# Schematic_DeLonghi_CP_structured.net
KiCad netlist of a schematic drawn in EasyEDA
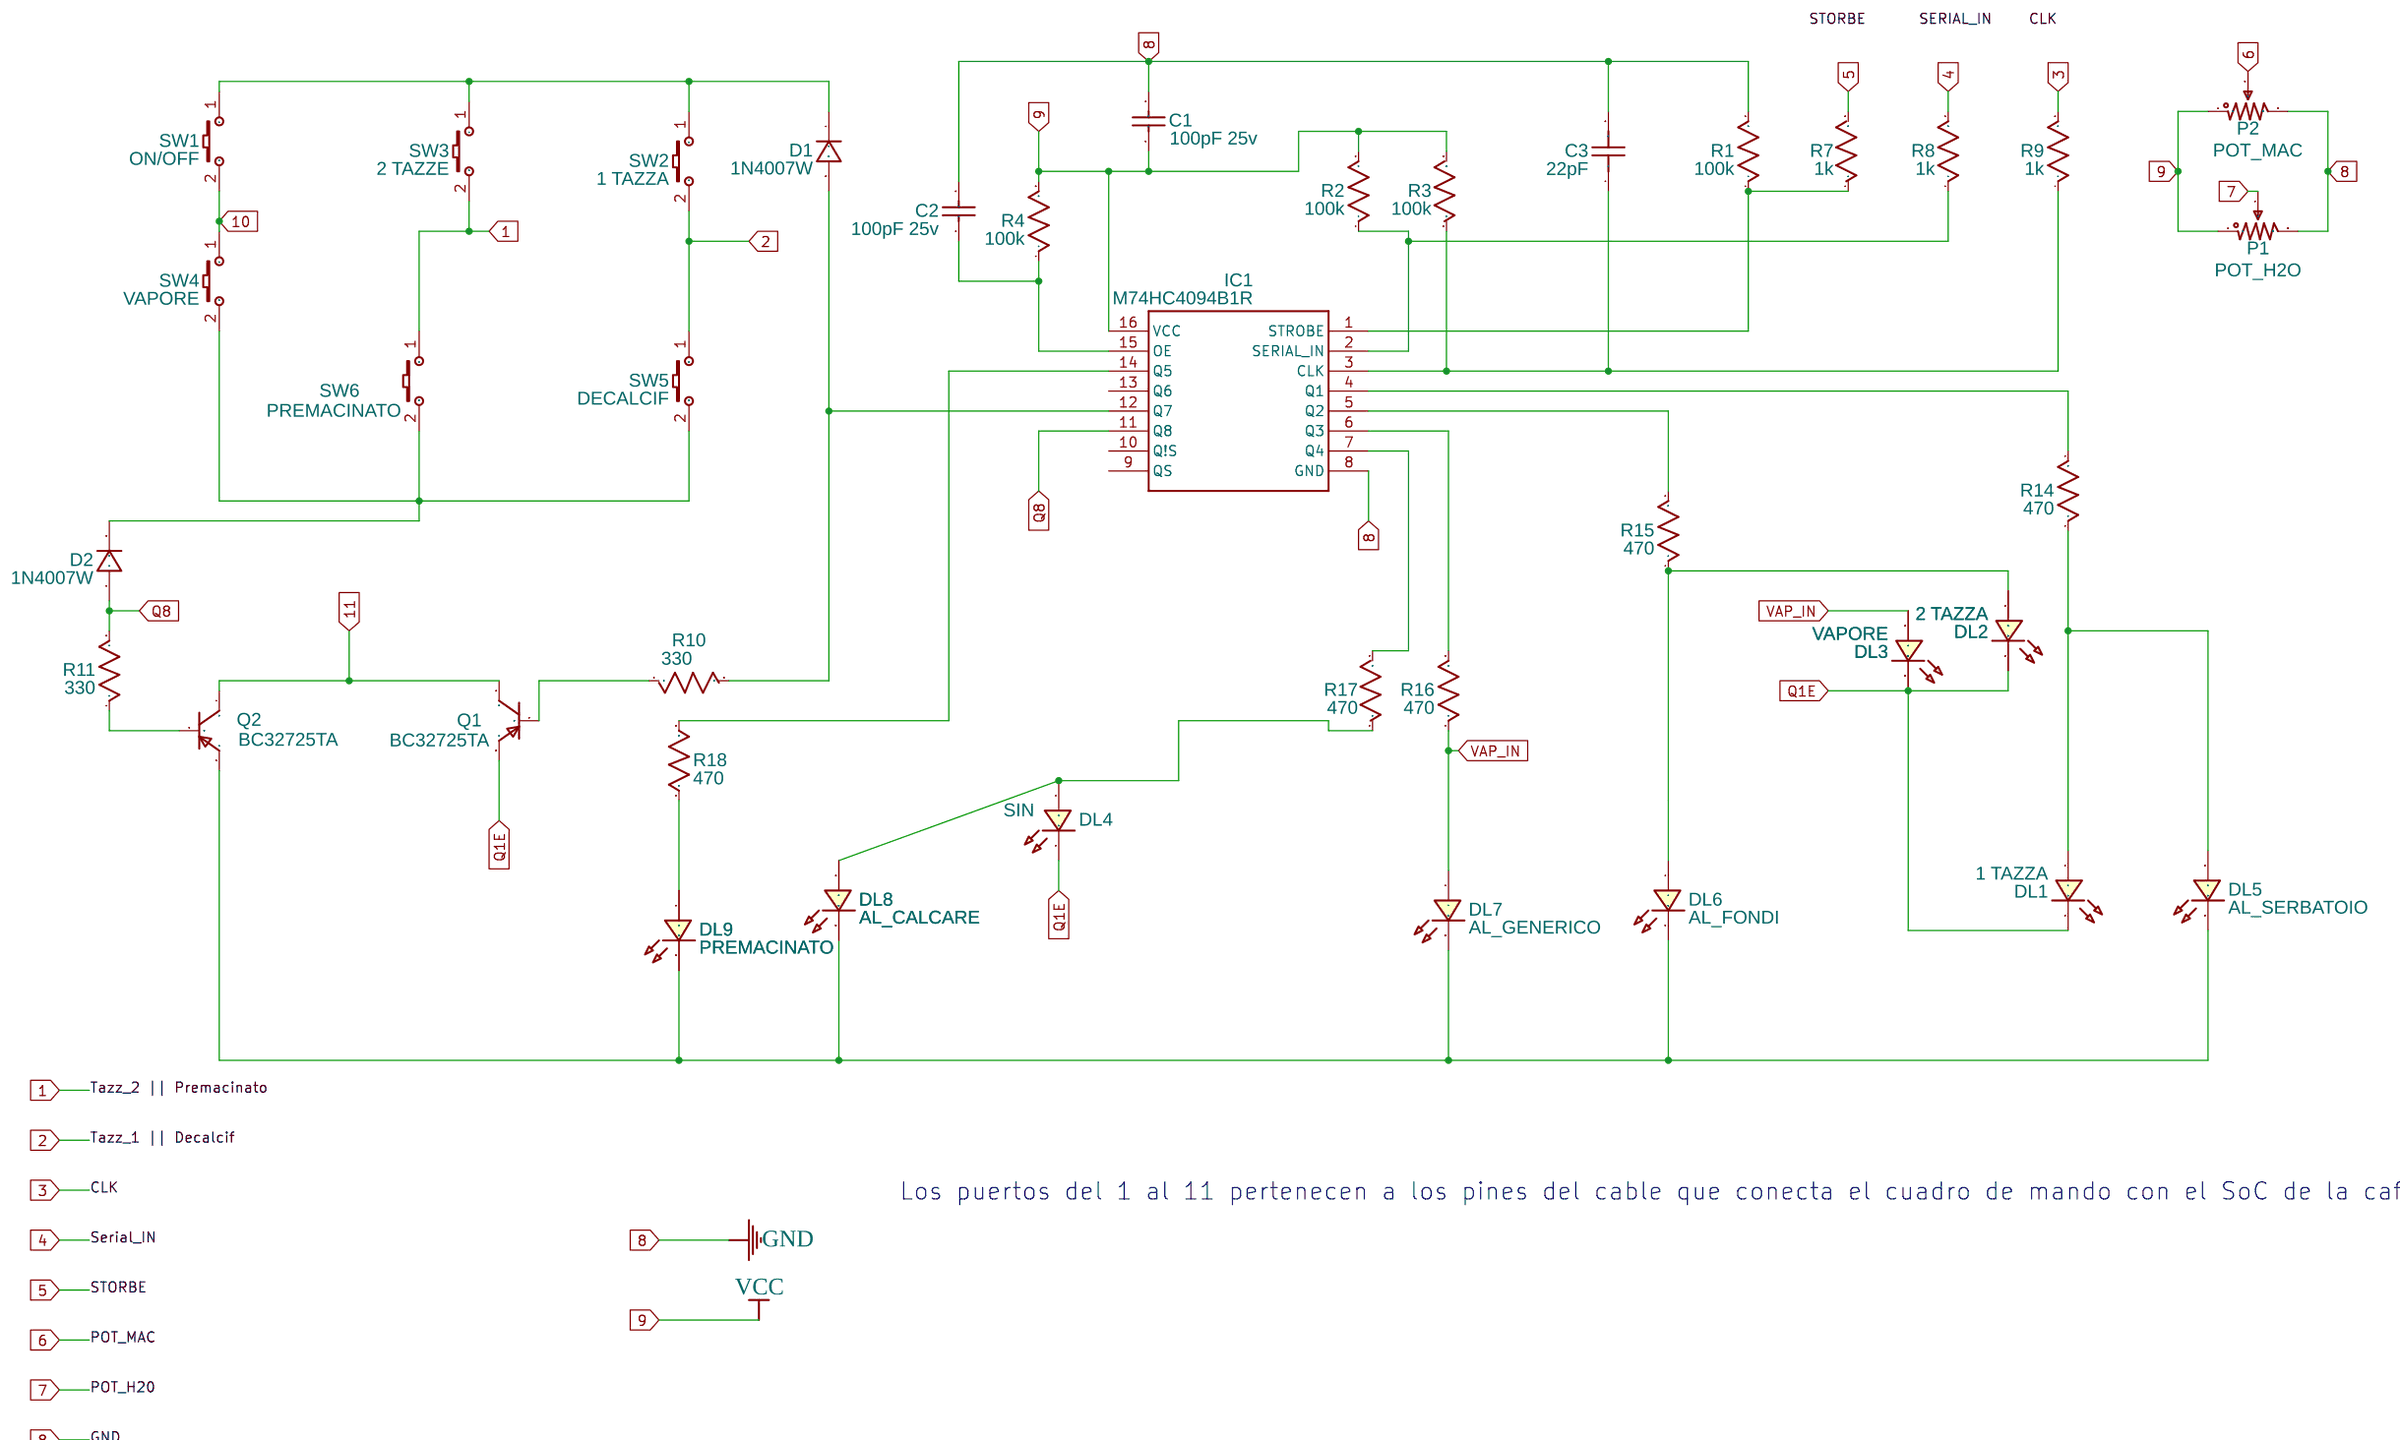
[diagram p0: schematic sheet]

(export (version "E")
  (design (tool "Eeschema 10.0.6"))
  (components
    (comp (ref "C1") (value "100pF 25v") (libsource (lib "") (part "100pF (101) 25V_1")))
    (comp (ref "C2") (value "100pF 25v") (libsource (lib "") (part "100pF (101) 25V")))
    (comp (ref "C3")
      (value "22pF")
      (fields
        (field (name "BOM_Manufacturer Part") "08051A220JAT2A")
        (field (name "BOM_Supplier Part") "C382073")
      )
      (libsource (lib "") (part "08051A220JAT2A"))
    )
    (comp (ref "D1")
      (value "1N4007W")
      (fields (field (name "BOM_Supplier Part") "C328592"))
      (libsource (lib "") (part "1N4007W"))
    )
    (comp (ref "D2")
      (value "1N4007W")
      (fields (field (name "BOM_Supplier Part") "C328592"))
      (libsource (lib "") (part "1N4007W"))
    )
    (comp (ref "DL1")
      (value "1 TAZZA")
      (fields
        (field (name "BOM_Manufacturer Part") "19-217/R6C-AL1M2VY/3T")
        (field (name "BOM_Supplier Part") "C72044")
      )
      (libsource (lib "") (part "LED-0603_R_1"))
    )
    (comp (ref "DL2")
      (value "2 TAZZA")
      (fields
        (field (name "BOM_Manufacturer Part") "19-217/R6C-AL1M2VY/3T")
        (field (name "BOM_Supplier Part") "C72044")
      )
      (libsource (lib "") (part "LED-0603_R_1"))
    )
    (comp (ref "DL3")
      (value "VAPORE")
      (fields
        (field (name "BOM_Manufacturer Part") "19-217/R6C-AL1M2VY/3T")
        (field (name "BOM_Supplier Part") "C72044")
      )
      (libsource (lib "") (part "LED-0603_R_1"))
    )
    (comp (ref "DL4")
      (value "SIN")
      (fields
        (field (name "BOM_Manufacturer Part") "19-217/R6C-AL1M2VY/3T")
        (field (name "BOM_Supplier Part") "C72044")
      )
      (libsource (lib "") (part "LED-0603_R"))
    )
    (comp (ref "DL5")
      (value "AL_SERBATOIO")
      (fields
        (field (name "BOM_Manufacturer Part") "19-217/R6C-AL1M2VY/3T")
        (field (name "BOM_Supplier Part") "C72044")
      )
      (libsource (lib "") (part "LED-0603_R"))
    )
    (comp (ref "DL6")
      (value "AL_FONDI")
      (fields
        (field (name "BOM_Manufacturer Part") "19-217/R6C-AL1M2VY/3T")
        (field (name "BOM_Supplier Part") "C72044")
      )
      (libsource (lib "") (part "LED-0603_R"))
    )
    (comp (ref "DL7")
      (value "AL_GENERICO")
      (fields
        (field (name "BOM_Manufacturer Part") "19-217/R6C-AL1M2VY/3T")
        (field (name "BOM_Supplier Part") "C72044")
      )
      (libsource (lib "") (part "LED-0603_R"))
    )
    (comp (ref "DL8")
      (value "AL_CALCARE")
      (fields
        (field (name "BOM_Manufacturer Part") "19-217/R6C-AL1M2VY/3T")
        (field (name "BOM_Supplier Part") "C72044")
      )
      (libsource (lib "") (part "LED-0603_R"))
    )
    (comp (ref "DL9")
      (value "PREMACINATO")
      (fields
        (field (name "BOM_Manufacturer Part") "19-217/R6C-AL1M2VY/3T")
        (field (name "BOM_Supplier Part") "C72044")
      )
      (libsource (lib "") (part "LED-0603_R"))
    )
    (comp (ref "IC1") (value "M74HC4094B1R") (libsource (lib "") (part "M74HC4094B1R")))
    (comp (ref "P1") (value "POT_H2O") (libsource (lib "") (part "R_3386P_US")))
    (comp (ref "P2") (value "POT_MAC") (libsource (lib "") (part "R_3386P_US")))
    (comp (ref "Q1")
      (value "BC32725TA")
      (fields (field (name "BOM_Supplier Part") "C236948"))
      (libsource (lib "") (part "BC32725TA_1"))
    )
    (comp (ref "Q2")
      (value "BC32725TA")
      (fields (field (name "BOM_Supplier Part") "C236948"))
      (libsource (lib "") (part "BC32725TA"))
    )
    (comp (ref "R1") (value "100k") (libsource (lib "") (part "R_0201_US")))
    (comp (ref "R2") (value "100k") (libsource (lib "") (part "R_0201_US")))
    (comp (ref "R3") (value "100k") (libsource (lib "") (part "R_0201_US_1")))
    (comp (ref "R4") (value "100k") (libsource (lib "") (part "R_0201_US")))
    (comp (ref "R7") (value "1k") (libsource (lib "") (part "R_0201_US_1")))
    (comp (ref "R8") (value "1k") (libsource (lib "") (part "R_0201_US")))
    (comp (ref "R9") (value "1k") (libsource (lib "") (part "R_0201_US")))
    (comp (ref "R10") (value "330") (libsource (lib "") (part "R_0201_US_2")))
    (comp (ref "R11") (value "330") (libsource (lib "") (part "R_0201_US")))
    (comp (ref "R14") (value "470") (libsource (lib "") (part "R_0201_US")))
    (comp (ref "R15") (value "470") (libsource (lib "") (part "R_0201_US")))
    (comp (ref "R16") (value "470") (libsource (lib "") (part "R_0201_US")))
    (comp (ref "R17") (value "470") (libsource (lib "") (part "R_0201_US_1")))
    (comp (ref "R18") (value "470") (libsource (lib "") (part "R_0201_US_3")))
    (comp (ref "SW1")
      (value "ON/OFF")
      (fields
        (field (name "BOM_Manufacturer Part") "K2-1107ST-A4SW-06")
        (field (name "BOM_Supplier Part") "C118141")
      )
      (libsource (lib "") (part "K2-3.6×6.1_SMD"))
    )
    (comp (ref "SW2")
      (value "1 TAZZA")
      (fields
        (field (name "BOM_Manufacturer Part") "K2-1107ST-A4SW-06")
        (field (name "BOM_Supplier Part") "C118141")
      )
      (libsource (lib "") (part "K2-3.6×6.1_SMD"))
    )
    (comp (ref "SW3")
      (value "2 TAZZE")
      (fields
        (field (name "BOM_Manufacturer Part") "K2-1107ST-A4SW-06")
        (field (name "BOM_Supplier Part") "C118141")
      )
      (libsource (lib "") (part "K2-3.6×6.1_SMD"))
    )
    (comp (ref "SW4")
      (value "VAPORE")
      (fields
        (field (name "BOM_Manufacturer Part") "K2-1107ST-A4SW-06")
        (field (name "BOM_Supplier Part") "C118141")
      )
      (libsource (lib "") (part "K2-3.6×6.1_SMD"))
    )
    (comp (ref "SW5")
      (value "DECALCIF")
      (fields
        (field (name "BOM_Manufacturer Part") "K2-1107ST-A4SW-06")
        (field (name "BOM_Supplier Part") "C118141")
      )
      (libsource (lib "") (part "K2-3.6×6.1_SMD"))
    )
    (comp (ref "SW6")
      (value "PREMACINATO")
      (fields
        (field (name "BOM_Manufacturer Part") "K2-1107ST-A4SW-06")
        (field (name "BOM_Supplier Part") "C118141")
      )
      (libsource (lib "") (part "K2-3.6×6.1_SMD"))
    )
  )
  (nets
    (net (code "2") (name "1") (class "Default")
      (node (ref "SW3") (pin "2") (pinfunction "2_2") (pintype "unspecified"))
      (node (ref "SW6") (pin "1") (pinfunction "1_1") (pintype "unspecified"))
    )
    (net (code "3") (name "2") (class "Default")
      (node (ref "SW2") (pin "2") (pinfunction "2_2") (pintype "unspecified"))
      (node (ref "SW5") (pin "1") (pinfunction "1_1") (pintype "unspecified"))
    )
    (net (code "4") (name "3") (class "Default")
      (node (ref "R9") (pin "2") (pinfunction "2_2") (pintype "unspecified"))
    )
    (net (code "5") (name "4") (class "Default")
      (node (ref "R8") (pin "2") (pinfunction "2_2") (pintype "unspecified"))
    )
    (net (code "6") (name "5") (class "Default")
      (node (ref "R7") (pin "2") (pinfunction "2_2") (pintype "unspecified"))
    )
    (net (code "7") (name "6") (class "Default")
      (node (ref "P2") (pin "2") (pinfunction "2_2") (pintype "unspecified"))
    )
    (net (code "8") (name "7") (class "Default")
      (node (ref "P1") (pin "2") (pinfunction "2_2") (pintype "unspecified"))
    )
    (net (code "9") (name "8") (class "Default")
      (node (ref "C1") (pin "1") (pinfunction "1_1") (pintype "input"))
      (node (ref "C2") (pin "2") (pinfunction "2_2") (pintype "input"))
      (node (ref "C3") (pin "2") (pinfunction "2_2") (pintype "unspecified"))
      (node (ref "IC1") (pin "8") (pinfunction "GND_8") (pintype "bidirectional"))
      (node (ref "P1") (pin "3") (pinfunction "3_3") (pintype "unspecified"))
      (node (ref "P2") (pin "3") (pinfunction "3_3") (pintype "unspecified"))
      (node (ref "R1") (pin "2") (pinfunction "2_2") (pintype "unspecified"))
    )
    (net (code "10") (name "9") (class "Default")
      (node (ref "C1") (pin "2") (pinfunction "2_2") (pintype "input"))
      (node (ref "IC1") (pin "16") (pinfunction "VCC_16") (pintype "bidirectional"))
      (node (ref "P1") (pin "1") (pinfunction "1_1") (pintype "unspecified"))
      (node (ref "P2") (pin "1") (pinfunction "1_1") (pintype "unspecified"))
      (node (ref "R2") (pin "2") (pinfunction "2_2") (pintype "unspecified"))
      (node (ref "R3") (pin "2") (pinfunction "2_2") (pintype "unspecified"))
      (node (ref "R4") (pin "2") (pinfunction "2_2") (pintype "unspecified"))
    )
    (net (code "11") (name "10") (class "Default")
      (node (ref "SW1") (pin "2") (pinfunction "2_2") (pintype "unspecified"))
      (node (ref "SW4") (pin "1") (pinfunction "1_1") (pintype "unspecified"))
    )
    (net (code "12") (name "11") (class "Default")
      (node (ref "Q1") (pin "1") (pinfunction "C_1") (pintype "unspecified"))
      (node (ref "Q2") (pin "1") (pinfunction "C_1") (pintype "unspecified"))
    )
    (net (code "13") (name "Net-(D1-Pad1)") (class "Default")
      (node (ref "D1") (pin "1") (pinfunction "1_1") (pintype "unspecified"))
      (node (ref "SW1") (pin "1") (pinfunction "1_1") (pintype "unspecified"))
      (node (ref "SW2") (pin "1") (pinfunction "1_1") (pintype "unspecified"))
      (node (ref "SW3") (pin "1") (pinfunction "1_1") (pintype "unspecified"))
    )
    (net (code "14") (name "Net-(D2-Pad1)") (class "Default")
      (node (ref "D2") (pin "1") (pinfunction "1_1") (pintype "unspecified"))
      (node (ref "SW4") (pin "2") (pinfunction "2_2") (pintype "unspecified"))
      (node (ref "SW5") (pin "2") (pinfunction "2_2") (pintype "unspecified"))
      (node (ref "SW6") (pin "2") (pinfunction "2_2") (pintype "unspecified"))
    )
    (net (code "15") (name "Net-(DL1-Pad1)") (class "Default")
      (node (ref "DL1") (pin "1") (pinfunction "1_1") (pintype "unspecified"))
      (node (ref "DL5") (pin "1") (pinfunction "1_1") (pintype "unspecified"))
      (node (ref "R14") (pin "1") (pinfunction "1_1") (pintype "unspecified"))
    )
    (net (code "16") (name "Net-(DL2-Pad1)") (class "Default")
      (node (ref "DL2") (pin "1") (pinfunction "1_1") (pintype "unspecified"))
      (node (ref "DL6") (pin "1") (pinfunction "1_1") (pintype "unspecified"))
      (node (ref "R15") (pin "1") (pinfunction "1_1") (pintype "unspecified"))
    )
    (net (code "17") (name "Net-(DL4-Pad1)") (class "Default")
      (node (ref "DL4") (pin "1") (pinfunction "1_1") (pintype "unspecified"))
      (node (ref "DL8") (pin "1") (pinfunction "1_1") (pintype "unspecified"))
      (node (ref "R17") (pin "1") (pinfunction "1_1") (pintype "unspecified"))
    )
    (net (code "18") (name "Net-(DL9-Pad1)") (class "Default")
      (node (ref "DL9") (pin "1") (pinfunction "1_1") (pintype "unspecified"))
      (node (ref "R18") (pin "1") (pinfunction "1_1") (pintype "unspecified"))
    )
    (net (code "19") (name "Net-(IC1-CLK)") (class "Default")
      (node (ref "C3") (pin "1") (pinfunction "1_1") (pintype "unspecified"))
      (node (ref "IC1") (pin "3") (pinfunction "CLK_3") (pintype "bidirectional"))
      (node (ref "R3") (pin "1") (pinfunction "1_1") (pintype "unspecified"))
      (node (ref "R9") (pin "1") (pinfunction "1_1") (pintype "unspecified"))
    )
    (net (code "20") (name "Net-(IC1-OE)") (class "Default")
      (node (ref "C2") (pin "1") (pinfunction "1_1") (pintype "input"))
      (node (ref "IC1") (pin "15") (pinfunction "OE_15") (pintype "bidirectional"))
      (node (ref "R4") (pin "1") (pinfunction "1_1") (pintype "unspecified"))
    )
    (net (code "21") (name "Net-(IC1-Q1)") (class "Default")
      (node (ref "IC1") (pin "4") (pinfunction "Q1_4") (pintype "bidirectional"))
      (node (ref "R14") (pin "2") (pinfunction "2_2") (pintype "unspecified"))
    )
    (net (code "22") (name "Net-(IC1-Q2)") (class "Default")
      (node (ref "IC1") (pin "5") (pinfunction "Q2_5") (pintype "bidirectional"))
      (node (ref "R15") (pin "2") (pinfunction "2_2") (pintype "unspecified"))
    )
    (net (code "23") (name "Net-(IC1-Q3)") (class "Default")
      (node (ref "IC1") (pin "6") (pinfunction "Q3_6") (pintype "bidirectional"))
      (node (ref "R16") (pin "2") (pinfunction "2_2") (pintype "unspecified"))
    )
    (net (code "24") (name "Net-(IC1-Q4)") (class "Default")
      (node (ref "IC1") (pin "7") (pinfunction "Q4_7") (pintype "bidirectional"))
      (node (ref "R17") (pin "2") (pinfunction "2_2") (pintype "unspecified"))
    )
    (net (code "25") (name "Net-(IC1-Q5)") (class "Default")
      (node (ref "IC1") (pin "14") (pinfunction "Q5_14") (pintype "bidirectional"))
      (node (ref "R18") (pin "2") (pinfunction "2_2") (pintype "unspecified"))
    )
    (net (code "26") (name "Net-(IC1-Q7)") (class "Default")
      (node (ref "D1") (pin "2") (pinfunction "2_2") (pintype "unspecified"))
      (node (ref "IC1") (pin "12") (pinfunction "Q7_12") (pintype "bidirectional"))
      (node (ref "R10") (pin "2") (pinfunction "2_2") (pintype "unspecified"))
    )
    (net (code "27") (name "Net-(IC1-SERIAL_IN)") (class "Default")
      (node (ref "IC1") (pin "2") (pinfunction "SERIAL_IN_2") (pintype "bidirectional"))
      (node (ref "R2") (pin "1") (pinfunction "1_1") (pintype "unspecified"))
      (node (ref "R8") (pin "1") (pinfunction "1_1") (pintype "unspecified"))
    )
    (net (code "28") (name "Net-(IC1-STROBE)") (class "Default")
      (node (ref "IC1") (pin "1") (pinfunction "STROBE_1") (pintype "bidirectional"))
      (node (ref "R1") (pin "1") (pinfunction "1_1") (pintype "unspecified"))
      (node (ref "R7") (pin "1") (pinfunction "1_1") (pintype "unspecified"))
    )
    (net (code "29") (name "Net-(Q1-B)") (class "Default")
      (node (ref "Q1") (pin "2") (pinfunction "B_2") (pintype "unspecified"))
      (node (ref "R10") (pin "1") (pinfunction "1_1") (pintype "unspecified"))
    )
    (net (code "30") (name "Net-(Q2-B)") (class "Default")
      (node (ref "Q2") (pin "2") (pinfunction "B_2") (pintype "unspecified"))
      (node (ref "R11") (pin "1") (pinfunction "1_1") (pintype "unspecified"))
    )
    (net (code "31") (name "Net-(Q2-E)") (class "Default")
      (node (ref "DL5") (pin "2") (pinfunction "2_2") (pintype "unspecified"))
      (node (ref "DL6") (pin "2") (pinfunction "2_2") (pintype "unspecified"))
      (node (ref "DL7") (pin "2") (pinfunction "2_2") (pintype "unspecified"))
      (node (ref "DL8") (pin "2") (pinfunction "2_2") (pintype "unspecified"))
      (node (ref "DL9") (pin "2") (pinfunction "2_2") (pintype "unspecified"))
      (node (ref "Q2") (pin "3") (pinfunction "E_3") (pintype "unspecified"))
    )
    (net (code "32") (name "Q1E") (class "Default")
      (node (ref "DL1") (pin "2") (pinfunction "2_2") (pintype "unspecified"))
      (node (ref "DL2") (pin "2") (pinfunction "2_2") (pintype "unspecified"))
      (node (ref "DL3") (pin "2") (pinfunction "2_2") (pintype "unspecified"))
      (node (ref "DL4") (pin "2") (pinfunction "2_2") (pintype "unspecified"))
      (node (ref "Q1") (pin "3") (pinfunction "E_3") (pintype "unspecified"))
    )
    (net (code "33") (name "Q8") (class "Default")
      (node (ref "D2") (pin "2") (pinfunction "2_2") (pintype "unspecified"))
      (node (ref "IC1") (pin "11") (pinfunction "Q8_11") (pintype "bidirectional"))
      (node (ref "R11") (pin "2") (pinfunction "2_2") (pintype "unspecified"))
    )
    (net (code "34") (name "VAP_IN") (class "Default")
      (node (ref "DL3") (pin "1") (pinfunction "1_1") (pintype "unspecified"))
      (node (ref "DL7") (pin "1") (pinfunction "1_1") (pintype "unspecified"))
      (node (ref "R16") (pin "1") (pinfunction "1_1") (pintype "unspecified"))
    )
    (net (code "35") (name "unconnected-(IC1-Q!S-Pad10)") (class "Default")
      (node (ref "IC1") (pin "10") (pinfunction "Q!S_10") (pintype "bidirectional"))
    )
    (net (code "36") (name "unconnected-(IC1-Q6-Pad13)") (class "Default")
      (node (ref "IC1") (pin "13") (pinfunction "Q6_13") (pintype "bidirectional"))
    )
    (net (code "37") (name "unconnected-(IC1-QS-Pad9)") (class "Default")
      (node (ref "IC1") (pin "9") (pinfunction "QS_9") (pintype "bidirectional"))
    )
  )
)
